# Breadboard_Power_Module.net
KiCad netlist of a schematic drawn in Altium Designer
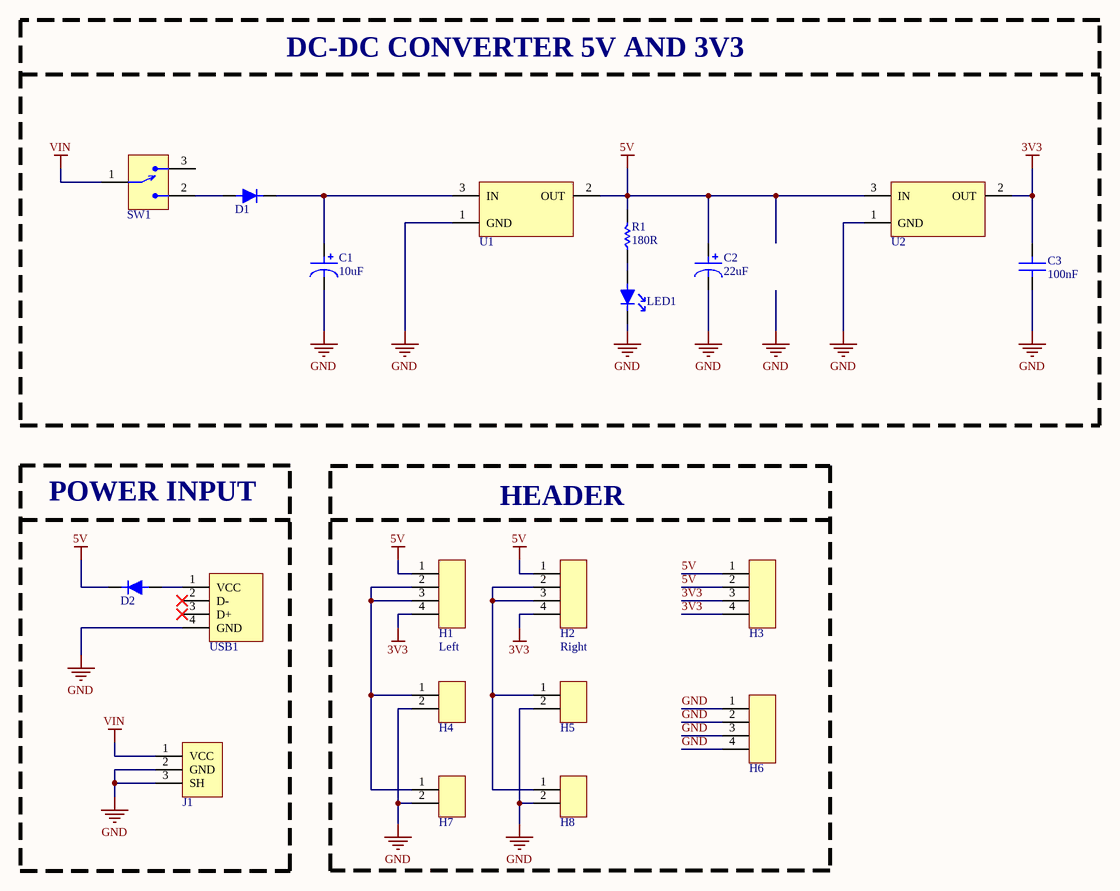
[diagram p0: Breadboard Power Module.SchDoc]

(export (version "E")
  (design (tool "Eeschema 10.0.6"))
  (components
    (comp (ref "C1")
      (value "10uF")
      (footprint "CAP ALUM")
      (description "CAP ALUM 10UF 20% 50V SMD")
      (fields (field (name "Comment") "EEH-ZA1H100R"))
      (libsource (lib "Breadboard Power Module") (part "CAP ALUM 10uF SMD"))
    )
    (comp (ref "C2")
      (value "22uF")
      (footprint "CAP ALUM")
      (description "CAP ALUM 22UF 20% 35V SMD")
      (fields (field (name "Comment") "35SVPF22M"))
      (libsource (lib "Breadboard Power Module") (part "CAP ALUM 22uF SMD"))
    )
    (comp (ref "C3")
      (value "100nF")
      (footprint "CAP 0805")
      (description "CAP CER 0.1UF 50V X7R 0805")
      (fields
        (field (name "MANUFACTURER") "Yageo")
        (field (name "MANUFACTURER PART NUMBER") "CC0805KRX7R9BB104")
      )
      (libsource (lib "Breadboard Power Module") (part "CAP CER 0.1uF 0805"))
    )
    (comp (ref "D1")
      (value "MBR230LSFT1G")
      (footprint "DIODE")
      (description "DIODE SCHOTTKY 30V 2A")
      (fields
        (field (name "MANUFACTURER") "Sangdest Microelectronics")
        (field (name "MANUFACTURER PART NUMBER") "1N4007FL")
      )
      (libsource (lib "Breadboard Power Module") (part "DIODE SMD"))
    )
    (comp (ref "D2")
      (value "MBR230LSFT1G")
      (footprint "DIODE")
      (description "DIODE SCHOTTKY 30V 2A")
      (fields
        (field (name "MANUFACTURER") "Sangdest Microelectronics")
        (field (name "MANUFACTURER PART NUMBER") "1N4007FL")
      )
      (libsource (lib "Breadboard Power Module") (part "DIODE SMD"))
    )
    (comp (ref "H1")
      (value "61300411121")
      (footprint "HEADER 4 POS")
      (description "CONN HEADER VERT 4POS 2.54MM")
      (fields (field (name "MANUFACTURER") "Wurth Electronics"))
      (libsource (lib "Breadboard Power Module") (part "HEADER TH 4 POS"))
    )
    (comp (ref "H2")
      (value "61300411121")
      (footprint "HEADER 4 POS")
      (description "CONN HEADER VERT 4POS 2.54MM")
      (fields (field (name "MANUFACTURER") "Wurth Electronics"))
      (libsource (lib "Breadboard Power Module") (part "HEADER TH 4 POS"))
    )
    (comp (ref "H3")
      (value "61300411121")
      (footprint "HEADER 4 POS")
      (description "CONN HEADER VERT 4POS 2.54MM")
      (fields (field (name "MANUFACTURER") "Wurth Electronics"))
      (libsource (lib "Breadboard Power Module") (part "HEADER TH 4 POS"))
    )
    (comp (ref "H4")
      (value "61300211121")
      (footprint "HEADER 2 POS")
      (description "CONN HEADER VERT 2POS 2.54MM")
      (libsource (lib "Breadboard Power Module") (part "HEADER TH 2 POS"))
    )
    (comp (ref "H5")
      (value "61300211121")
      (footprint "HEADER 2 POS")
      (description "CONN HEADER VERT 2POS 2.54MM")
      (libsource (lib "Breadboard Power Module") (part "HEADER TH 2 POS"))
    )
    (comp (ref "H6")
      (value "61300411121")
      (footprint "HEADER 4 POS")
      (description "CONN HEADER VERT 4POS 2.54MM")
      (fields (field (name "MANUFACTURER") "Wurth Electronics"))
      (libsource (lib "Breadboard Power Module") (part "HEADER TH 4 POS"))
    )
    (comp (ref "H7")
      (value "61300211121")
      (footprint "HEADER 2 POS")
      (description "CONN HEADER VERT 2POS 2.54MM")
      (libsource (lib "Breadboard Power Module") (part "HEADER TH 2 POS"))
    )
    (comp (ref "H8")
      (value "61300211121")
      (footprint "HEADER 2 POS")
      (description "CONN HEADER VERT 2POS 2.54MM")
      (libsource (lib "Breadboard Power Module") (part "HEADER TH 2 POS"))
    )
    (comp (ref "J1")
      (value "54-00167")
      (footprint "POWER JACK")
      (description "CONN JACK R/A PCB 5.5X2.5MM")
      (libsource (lib "Breadboard Power Module") (part "POWER JACK"))
    )
    (comp (ref "LED1")
      (value "151031VS06000")
      (footprint "LED DIODE")
      (description "LED GREEN 3MM ROUND T/H")
      (fields (field (name "MANUFACTURER") "Wurth Electronics"))
      (libsource (lib "Breadboard Power Module") (part "GREEN LED TH"))
    )
    (comp (ref "R1")
      (value "180R")
      (footprint "RES 0603")
      (description "RES 180 OHM 5% 1/10W 0603")
      (fields
        (field (name "MANUFACTURER") "Stackpole Electronics")
        (field (name "MANUFACTURER PART NUMBER") "RNCF0603DTE330R")
      )
      (libsource (lib "Breadboard Power Module") (part "RES 180 OHM 0603"))
    )
    (comp (ref "SW1")
      (value "450301014042")
      (footprint "SLIDE SWITCH")
      (description "SWITCH SLIDE SPDT 500MA 12V")
      (fields (field (name "MANUFACTURER") "Wurth Electronics"))
      (libsource (lib "Breadboard Power Module") (part "SLIDE SWITCH"))
    )
    (comp (ref "U1")
      (value "AMS1117-5.0")
      (footprint "LDO 5V")
      (description "IC LDO REG 5V 1A SOT223")
      (libsource (lib "Breadboard Power Module") (part "LDO 5V SMD"))
    )
    (comp (ref "U2")
      (value "AMS1117-3.3")
      (footprint "LDO 3V3")
      (description "IC LDO REG 3.3V 1A SOT223")
      (libsource (lib "Breadboard Power Module") (part "LDO 3V3 SMD"))
    )
    (comp (ref "USB1")
      (value "USB-A1HSW6")
      (footprint "USB")
      (description "CONN RCPT TYPEA 4POS R/A")
      (fields (field (name "MANUFACTURER") "On-Shore Technology"))
      (libsource (lib "Breadboard Power Module") (part "USB TYPE-A"))
    )
  )
  (nets
    (net (code "1") (name "3V3") (class "Default")
      (node (ref "C3") (pin "2") (pinfunction "2_2") (pintype "passive"))
      (node (ref "H1") (pin "4") (pinfunction "4_4") (pintype "passive"))
      (node (ref "H2") (pin "4") (pinfunction "4_4") (pintype "passive"))
      (node (ref "H3") (pin "3") (pinfunction "3_3") (pintype "passive"))
      (node (ref "H3") (pin "4") (pinfunction "4_4") (pintype "passive"))
      (node (ref "U2") (pin "2") (pinfunction "OUT_2") (pintype "passive"))
    )
    (net (code "2") (name "5V") (class "Default")
      (node (ref "C2") (pin "1") (pintype "passive"))
      (node (ref "D2") (pin "2") (pinfunction "2_2") (pintype "passive"))
      (node (ref "H1") (pin "1") (pinfunction "1_1") (pintype "passive"))
      (node (ref "H2") (pin "1") (pinfunction "1_1") (pintype "passive"))
      (node (ref "H3") (pin "1") (pinfunction "1_1") (pintype "passive"))
      (node (ref "H3") (pin "2") (pinfunction "2_2") (pintype "passive"))
      (node (ref "R1") (pin "2") (pinfunction "2_2") (pintype "passive"))
      (node (ref "U1") (pin "2") (pinfunction "OUT_2") (pintype "passive"))
      (node (ref "U2") (pin "3") (pinfunction "IN_3") (pintype "passive"))
    )
    (net (code "3") (name "GND") (class "Default")
      (node (ref "C1") (pin "2") (pintype "passive"))
      (node (ref "C2") (pin "2") (pintype "passive"))
      (node (ref "C3") (pin "1") (pinfunction "1_1") (pintype "passive"))
      (node (ref "H4") (pin "2") (pinfunction "2_2") (pintype "passive"))
      (node (ref "H5") (pin "2") (pinfunction "2_2") (pintype "passive"))
      (node (ref "H6") (pin "1") (pinfunction "1_1") (pintype "passive"))
      (node (ref "H6") (pin "2") (pinfunction "2_2") (pintype "passive"))
      (node (ref "H6") (pin "3") (pinfunction "3_3") (pintype "passive"))
      (node (ref "H6") (pin "4") (pinfunction "4_4") (pintype "passive"))
      (node (ref "H7") (pin "2") (pinfunction "2_2") (pintype "passive"))
      (node (ref "H8") (pin "2") (pinfunction "2_2") (pintype "passive"))
      (node (ref "J1") (pin "2") (pinfunction "GND_2") (pintype "passive"))
      (node (ref "J1") (pin "3") (pinfunction "SH_3") (pintype "passive"))
      (node (ref "LED1") (pin "2") (pinfunction "2_2") (pintype "passive"))
      (node (ref "U1") (pin "1") (pinfunction "GND_1") (pintype "passive"))
      (node (ref "U2") (pin "1") (pinfunction "GND_1") (pintype "passive"))
      (node (ref "USB1") (pin "4") (pinfunction "GND_4") (pintype "passive"))
    )
    (net (code "4") (name "Net-(D1-Pad1)") (class "Default")
      (node (ref "D1") (pin "1") (pinfunction "1_1") (pintype "passive"))
      (node (ref "SW1") (pin "2") (pinfunction "2_2") (pintype "passive"))
    )
    (net (code "5") (name "Net-(H1-Pad2)") (class "Default")
      (node (ref "H1") (pin "2") (pinfunction "2_2") (pintype "passive"))
      (node (ref "H1") (pin "3") (pinfunction "3_3") (pintype "passive"))
      (node (ref "H4") (pin "1") (pinfunction "1_1") (pintype "passive"))
      (node (ref "H7") (pin "1") (pinfunction "1_1") (pintype "passive"))
    )
    (net (code "6") (name "Net-(H2-Pad2)") (class "Default")
      (node (ref "H2") (pin "2") (pinfunction "2_2") (pintype "passive"))
      (node (ref "H2") (pin "3") (pinfunction "3_3") (pintype "passive"))
      (node (ref "H5") (pin "1") (pinfunction "1_1") (pintype "passive"))
      (node (ref "H8") (pin "1") (pinfunction "1_1") (pintype "passive"))
    )
    (net (code "7") (name "Net-(LED1-Pad1)") (class "Default")
      (node (ref "LED1") (pin "1") (pinfunction "1_1") (pintype "passive"))
      (node (ref "R1") (pin "1") (pinfunction "1_1") (pintype "passive"))
    )
    (net (code "8") (name "Net-(U1-IN)") (class "Default")
      (node (ref "C1") (pin "1") (pintype "passive"))
      (node (ref "D1") (pin "2") (pinfunction "2_2") (pintype "passive"))
      (node (ref "U1") (pin "3") (pinfunction "IN_3") (pintype "passive"))
    )
    (net (code "9") (name "Net-(USB1-VCC)") (class "Default")
      (node (ref "D2") (pin "1") (pinfunction "1_1") (pintype "passive"))
      (node (ref "USB1") (pin "1") (pinfunction "VCC_1") (pintype "passive"))
    )
    (net (code "10") (name "VIN") (class "Default")
      (node (ref "J1") (pin "1") (pinfunction "VCC_1") (pintype "passive"))
      (node (ref "SW1") (pin "1") (pinfunction "1_1") (pintype "passive"))
    )
    (net (code "11") (name "unconnected-(SW1-Pad3)") (class "Default")
      (node (ref "SW1") (pin "3") (pinfunction "3_3") (pintype "passive"))
    )
    (net (code "12") (name "unconnected-(USB1-D+-Pad3)") (class "Default")
      (node (ref "USB1") (pin "3") (pinfunction "D+_3") (pintype "passive+no_connect"))
    )
    (net (code "13") (name "unconnected-(USB1-D--Pad2)") (class "Default")
      (node (ref "USB1") (pin "2") (pinfunction "D-_2") (pintype "passive+no_connect"))
    )
  )
)
